# CONFIGURATION___STORAGE___USER_LEDS_BUTT.net
KiCad netlist of a schematic drawn in Altium Designer
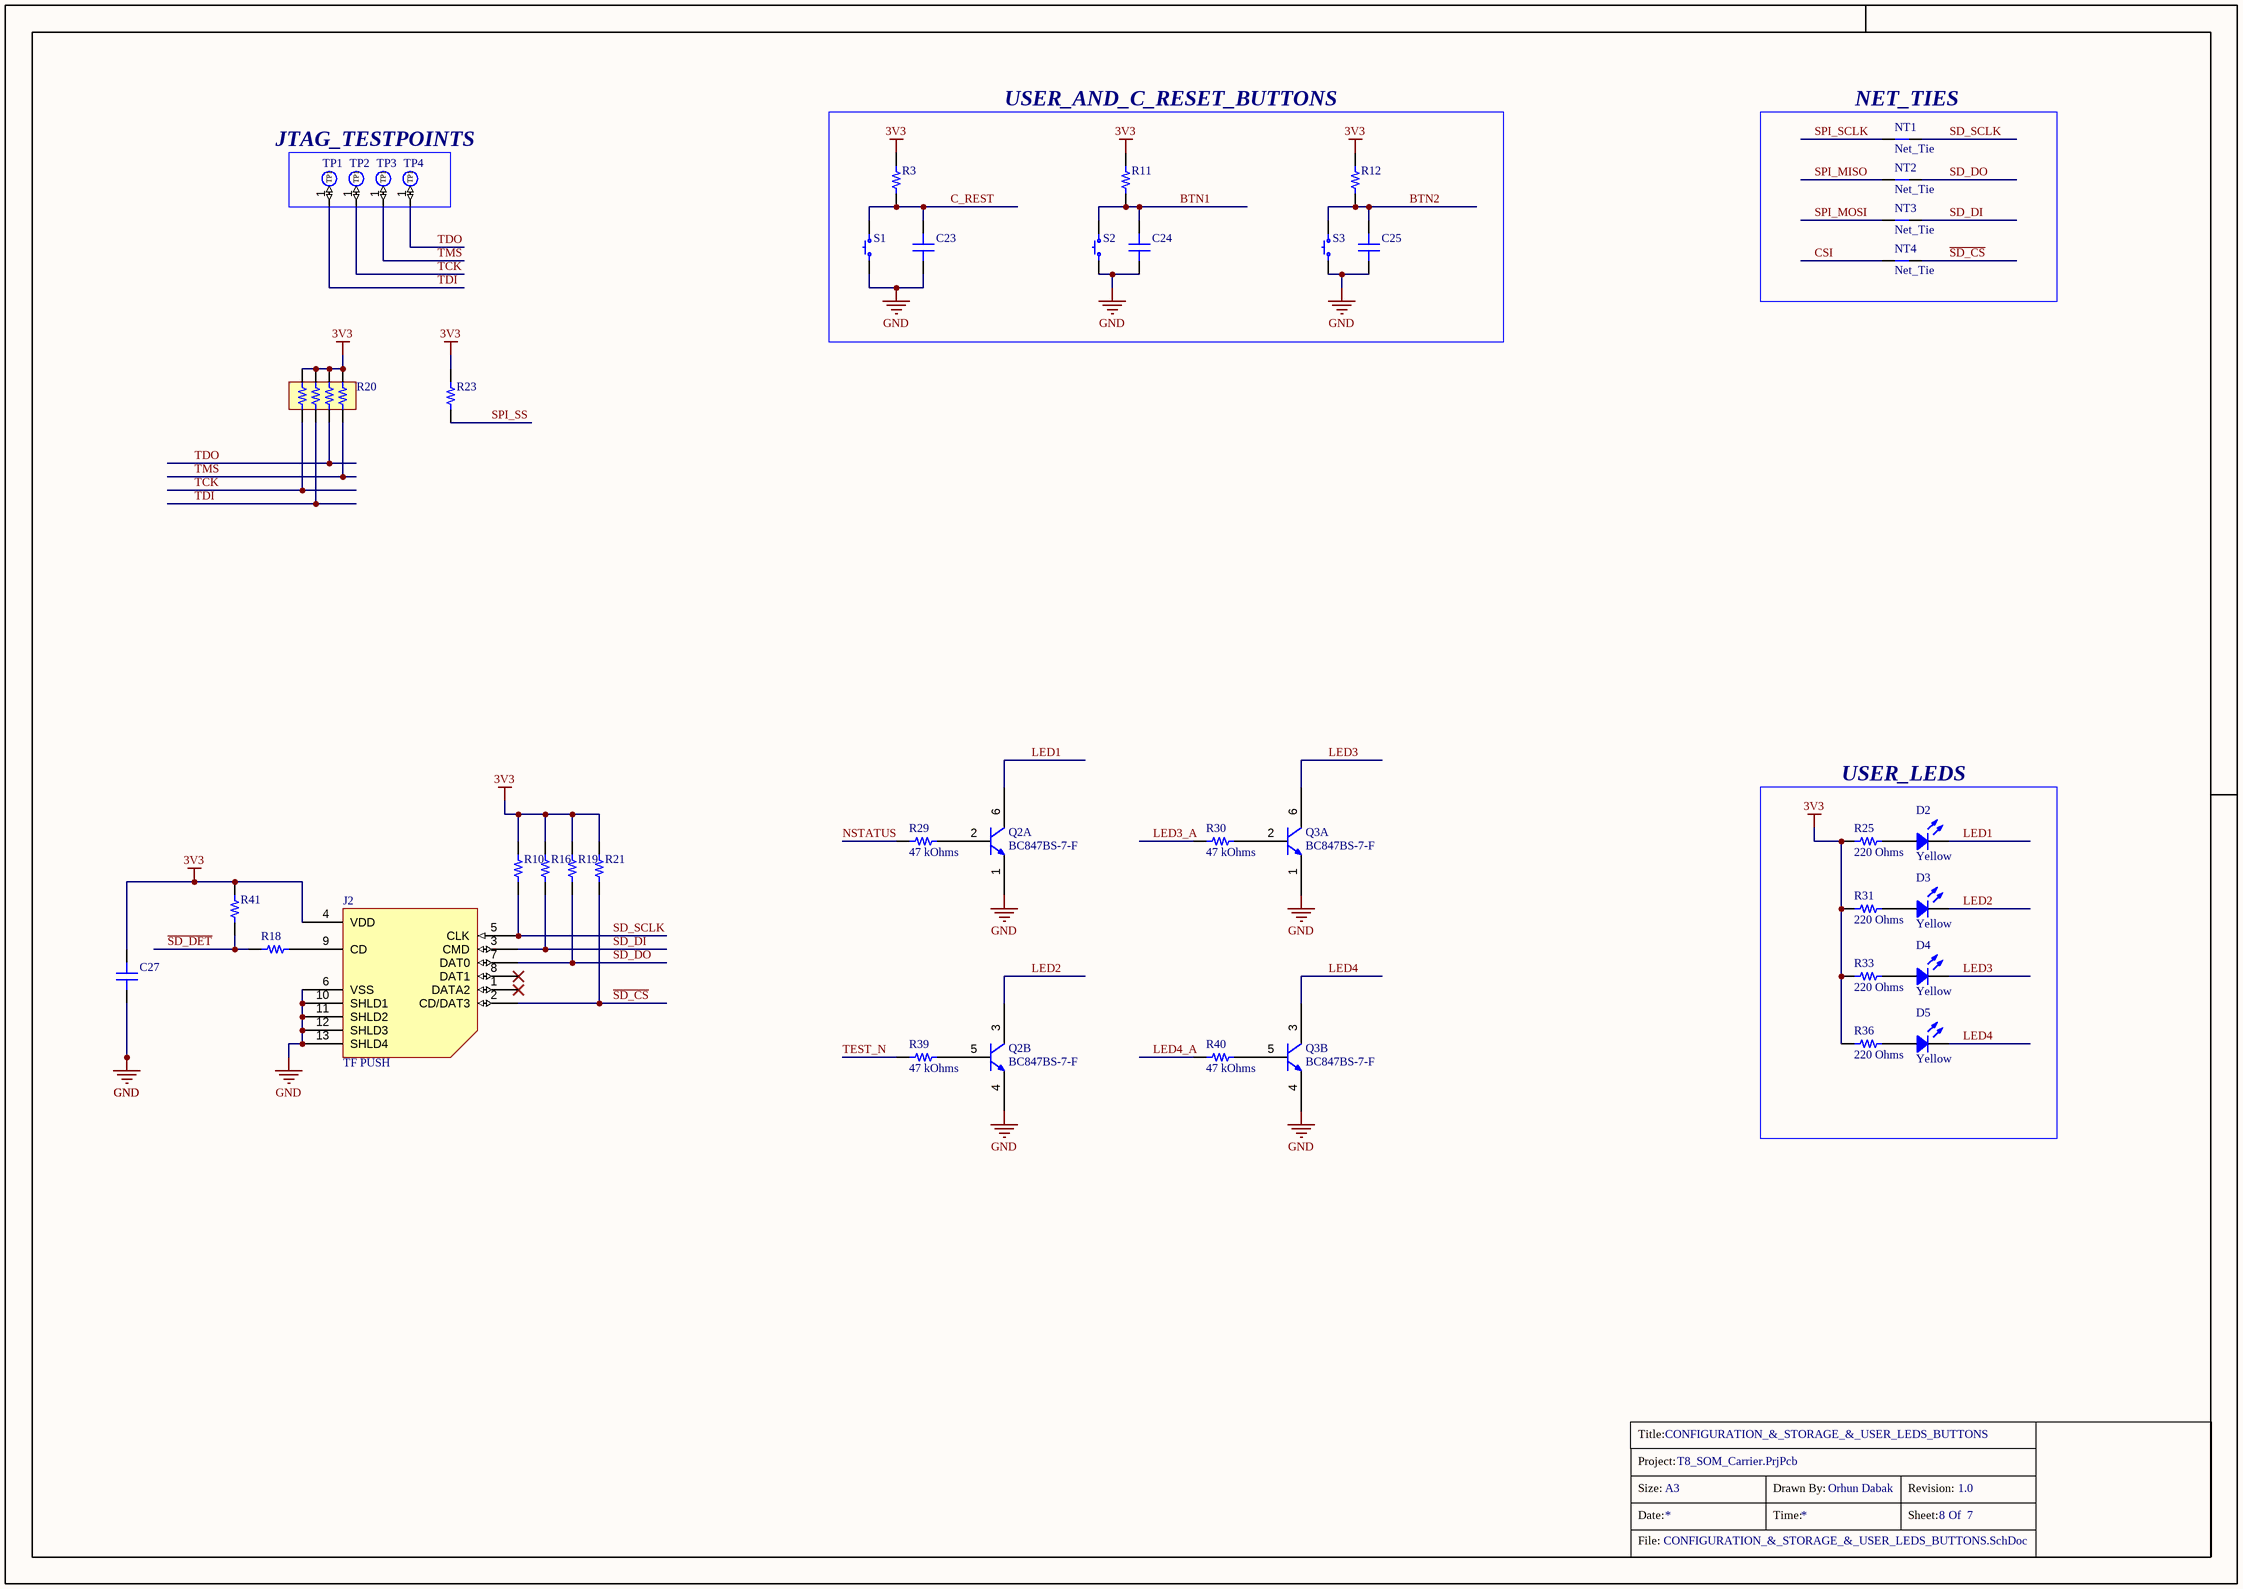
[diagram p0: CONFIGURATION_&_STORAGE_&_USER_LEDS_BUTTONS.SchDoc]

(export (version "E")
  (design (tool "Eeschema 10.0.6"))
  (components
    (comp (ref "C23")
      (value "10 µF")
      (footprint "CAP 0402_1005")
      (description "CAP CER 10UF 10V X5R 0402")
      (fields
        (field (name "PART NUMBER") "GRM155R61A106ME11D")
        (field (name "MANUFACTURER") "Murata Electronics")
      )
      (libsource (lib "Celestial Altium Library - altium_library") (part "Capacitor"))
    )
    (comp (ref "C24")
      (value "10 µF")
      (footprint "CAP 0402_1005")
      (description "CAP CER 10UF 10V X5R 0402")
      (fields
        (field (name "PART NUMBER") "GRM155R61A106ME11D")
        (field (name "MANUFACTURER") "Murata Electronics")
      )
      (libsource (lib "Celestial Altium Library - altium_library") (part "Capacitor"))
    )
    (comp (ref "C25")
      (value "10 µF")
      (footprint "CAP 0402_1005")
      (description "CAP CER 10UF 10V X5R 0402")
      (fields
        (field (name "PART NUMBER") "GRM155R61A106ME11D")
        (field (name "MANUFACTURER") "Murata Electronics")
      )
      (libsource (lib "Celestial Altium Library - altium_library") (part "Capacitor"))
    )
    (comp (ref "C27")
      (value "0.1 µF")
      (footprint "CAP 0402_1005")
      (description "CAP CER 0.1UF 10V X7R 0402")
      (fields (field (name "PART NUMBER") "CC0402KRX7R6BB104") (field (name "MANUFACTURER") "Yageo"))
      (libsource (lib "Celestial Altium Library - altium_library") (part "Capacitor"))
    )
    (comp (ref "D2")
      (value "Yellow")
      (footprint "LED 0603_1608 YELLOW")
      (description "LED YELLOW DIFFUSED SMD")
      (fields
        (field (name "PART NUMBER") "SML-LX0603YW-TR")
        (field (name "MANUFACTURER") "Lumex Opto/Components Inc.")
      )
      (libsource (lib "Celestial Altium Library - altium_library") (part "LED"))
    )
    (comp (ref "D3")
      (value "Yellow")
      (footprint "LED 0603_1608 YELLOW")
      (description "LED YELLOW DIFFUSED SMD")
      (fields
        (field (name "PART NUMBER") "SML-LX0603YW-TR")
        (field (name "MANUFACTURER") "Lumex Opto/Components Inc.")
      )
      (libsource (lib "Celestial Altium Library - altium_library") (part "LED"))
    )
    (comp (ref "D4")
      (value "Yellow")
      (footprint "LED 0603_1608 YELLOW")
      (description "LED YELLOW DIFFUSED SMD")
      (fields
        (field (name "PART NUMBER") "SML-LX0603YW-TR")
        (field (name "MANUFACTURER") "Lumex Opto/Components Inc.")
      )
      (libsource (lib "Celestial Altium Library - altium_library") (part "LED"))
    )
    (comp (ref "D5")
      (value "Yellow")
      (footprint "LED 0603_1608 YELLOW")
      (description "LED YELLOW DIFFUSED SMD")
      (fields
        (field (name "PART NUMBER") "SML-LX0603YW-TR")
        (field (name "MANUFACTURER") "Lumex Opto/Components Inc.")
      )
      (libsource (lib "Celestial Altium Library - altium_library") (part "LED"))
    )
    (comp (ref "J2")
      (value "TF PUSH")
      (footprint "TF PUSH")
      (description "-20℃~+90℃ 2mm Deck MicroSD card (TF card) Self bomb SMD SD Card Connectors ROHS")
      (fields (field (name "MANUFACTURER") "SHOU HAN") (field (name "LCSC PART NUMBER") "C393941"))
      (libsource (lib "T8_devkit_PCB") (part "TF PUSH"))
    )
    (comp (ref "NT1")
      (value "Net_Tie")
      (footprint "Net_Tie 0.2X0.2")
      (description "Net Tie")
      (libsource (lib "T8_devkit_PCB") (part "Net_Tie"))
    )
    (comp (ref "NT2")
      (value "Net_Tie")
      (footprint "Net_Tie 0.2X0.2")
      (description "Net Tie")
      (libsource (lib "T8_devkit_PCB") (part "Net_Tie"))
    )
    (comp (ref "NT3")
      (value "Net_Tie")
      (footprint "Net_Tie 0.2X0.2")
      (description "Net Tie")
      (libsource (lib "T8_devkit_PCB") (part "Net_Tie"))
    )
    (comp (ref "NT4")
      (value "Net_Tie")
      (footprint "Net_Tie 0.2X0.2")
      (description "Net Tie")
      (libsource (lib "T8_devkit_PCB") (part "Net_Tie"))
    )
    (comp (ref "Q2")
      (value "BC847BS-7-F")
      (footprint "BC847BS-7-F-Footprint-1")
      (description "2NPN Ic=100mA Vceo=45V hfe=200~450 P=200mW SOT363")
      (libsource (lib "Kocaeli University") (part "BC847BS-7-F-Symbol-1"))
    )
    (comp (ref "Q3")
      (value "BC847BS-7-F")
      (footprint "BC847BS-7-F-Footprint-1")
      (description "2NPN Ic=100mA Vceo=45V hfe=200~450 P=200mW SOT363")
      (libsource (lib "Kocaeli University") (part "BC847BS-7-F-Symbol-1"))
    )
    (comp (ref "R3")
      (value "10 kOhms")
      (footprint "RES 0201_0603")
      (description "RES 10K OHM 1% 1/20W 0201")
      (fields (field (name "PART NUMBER") "RC0201FR-0710KL") (field (name "MANUFACTURER") "Yageo"))
      (libsource (lib "Celestial Altium Library - altium_library") (part "Resistor"))
    )
    (comp (ref "R10")
      (value "10 kOhms")
      (footprint "RES 0201_0603")
      (description "RES SMD 10K OHM 1% 1/20W 0201")
      (fields (field (name "PART NUMBER") "CRCW020110K0FKED") (field (name "MANUFACTURER") "Vishay Dale"))
      (libsource (lib "Celestial Altium Library - altium_library") (part "Resistor"))
    )
    (comp (ref "R11")
      (value "10 kOhms")
      (footprint "RES 0201_0603")
      (description "RES 10K OHM 1% 1/20W 0201")
      (fields (field (name "PART NUMBER") "RC0201FR-0710KL") (field (name "MANUFACTURER") "Yageo"))
      (libsource (lib "Celestial Altium Library - altium_library") (part "Resistor"))
    )
    (comp (ref "R12")
      (value "10 kOhms")
      (footprint "RES 0201_0603")
      (description "RES 10K OHM 1% 1/20W 0201")
      (fields (field (name "PART NUMBER") "RC0201FR-0710KL") (field (name "MANUFACTURER") "Yageo"))
      (libsource (lib "Celestial Altium Library - altium_library") (part "Resistor"))
    )
    (comp (ref "R16")
      (value "10 kOhms")
      (footprint "RES 0201_0603")
      (description "RES SMD 10K OHM 1% 1/20W 0201")
      (fields (field (name "PART NUMBER") "CRCW020110K0FKED") (field (name "MANUFACTURER") "Vishay Dale"))
      (libsource (lib "Celestial Altium Library - altium_library") (part "Resistor"))
    )
    (comp (ref "R18")
      (value "0 Ohms")
      (footprint "RES 0201_0603")
      (description "RES 0 OHM JUMPER 1/20W 0201")
      (fields (field (name "PART NUMBER") "RC0201JR-070RL") (field (name "MANUFACTURER") "Yageo"))
      (libsource (lib "Celestial Altium Library - altium_library") (part "Resistor"))
    )
    (comp (ref "R19")
      (value "10 kOhms")
      (footprint "RES 0201_0603")
      (description "RES SMD 10K OHM 1% 1/20W 0201")
      (fields (field (name "PART NUMBER") "CRCW020110K0FKED") (field (name "MANUFACTURER") "Vishay Dale"))
      (libsource (lib "Celestial Altium Library - altium_library") (part "Resistor"))
    )
    (comp (ref "R20")
      (value "YC124-JR-0710KL")
      (footprint "RESNET 0804-8 CONVEX")
      (description "RES ARRAY 4 RES 10K OHM 0804")
      (fields (field (name "MANUFACTURER") "Yageo") (field (name "TOLERANCE") "±5%"))
      (libsource (lib "Celestial Altium Library - altium_library") (part "Resistor Array (4 circuit)"))
    )
    (comp (ref "R21")
      (value "10 kOhms")
      (footprint "RES 0201_0603")
      (description "RES SMD 10K OHM 1% 1/20W 0201")
      (fields (field (name "PART NUMBER") "CRCW020110K0FKED") (field (name "MANUFACTURER") "Vishay Dale"))
      (libsource (lib "Celestial Altium Library - altium_library") (part "Resistor"))
    )
    (comp (ref "R23")
      (value "10 kOhms")
      (footprint "RES 0201_0603")
      (description "RES 10K OHM 1% 1/20W 0201")
      (fields (field (name "PART NUMBER") "RC0201FR-0710KL") (field (name "MANUFACTURER") "Yageo"))
      (libsource (lib "Celestial Altium Library - altium_library") (part "Resistor"))
    )
    (comp (ref "R25")
      (value "220 Ohms")
      (footprint "RES 0402_1005")
      (description "RES 220 OHM 1% 1/16W 0402")
      (fields (field (name "PART NUMBER") "RC0402FR-07220RL") (field (name "MANUFACTURER") "Yageo"))
      (libsource (lib "Celestial Altium Library - altium_library") (part "Resistor"))
    )
    (comp (ref "R29")
      (value "47 kOhms")
      (footprint "RES 0201_0603")
      (description "RES 47K OHM 1% 1/20W 0201")
      (fields (field (name "PART NUMBER") "RC0201FR-0747KL") (field (name "MANUFACTURER") "Yageo"))
      (libsource (lib "Celestial Altium Library - altium_library") (part "Resistor"))
    )
    (comp (ref "R30")
      (value "47 kOhms")
      (footprint "RES 0201_0603")
      (description "RES 47K OHM 1% 1/20W 0201")
      (fields (field (name "PART NUMBER") "RC0201FR-0747KL") (field (name "MANUFACTURER") "Yageo"))
      (libsource (lib "Celestial Altium Library - altium_library") (part "Resistor"))
    )
    (comp (ref "R31")
      (value "220 Ohms")
      (footprint "RES 0402_1005")
      (description "RES 220 OHM 1% 1/16W 0402")
      (fields (field (name "PART NUMBER") "RC0402FR-07220RL") (field (name "MANUFACTURER") "Yageo"))
      (libsource (lib "Celestial Altium Library - altium_library") (part "Resistor"))
    )
    (comp (ref "R33")
      (value "220 Ohms")
      (footprint "RES 0402_1005")
      (description "RES 220 OHM 1% 1/16W 0402")
      (fields (field (name "PART NUMBER") "RC0402FR-07220RL") (field (name "MANUFACTURER") "Yageo"))
      (libsource (lib "Celestial Altium Library - altium_library") (part "Resistor"))
    )
    (comp (ref "R36")
      (value "220 Ohms")
      (footprint "RES 0402_1005")
      (description "RES 220 OHM 1% 1/16W 0402")
      (fields (field (name "PART NUMBER") "RC0402FR-07220RL") (field (name "MANUFACTURER") "Yageo"))
      (libsource (lib "Celestial Altium Library - altium_library") (part "Resistor"))
    )
    (comp (ref "R39")
      (value "47 kOhms")
      (footprint "RES 0201_0603")
      (description "RES 47K OHM 1% 1/20W 0201")
      (fields (field (name "PART NUMBER") "RC0201FR-0747KL") (field (name "MANUFACTURER") "Yageo"))
      (libsource (lib "Celestial Altium Library - altium_library") (part "Resistor"))
    )
    (comp (ref "R40")
      (value "47 kOhms")
      (footprint "RES 0201_0603")
      (description "RES 47K OHM 1% 1/20W 0201")
      (fields (field (name "PART NUMBER") "RC0201FR-0747KL") (field (name "MANUFACTURER") "Yageo"))
      (libsource (lib "Celestial Altium Library - altium_library") (part "Resistor"))
    )
    (comp (ref "R41")
      (value "100 kOhms")
      (footprint "RES 0201_0603")
      (description "RES SMD 100K OHM 1% 1/20W 0201")
      (fields
        (field (name "PART NUMBER") "CRG0201F100K")
        (field (name "MANUFACTURER") "TE Connectivity Passive Product")
      )
      (libsource (lib "Celestial Altium Library - altium_library") (part "Resistor"))
    )
    (comp (ref "S1")
      (value "TS342A2P-WZ")
      (footprint "TS342A2P-WZ")
      (fields (field (name "MANUFACTURER") "SHOU HAN") (field (name "JLCPCB PART NUMBER") "C557591"))
      (libsource (lib "T8_devkit_PCB") (part "TS342A2P-WZ"))
    )
    (comp (ref "S2")
      (value "TS342A2P-WZ")
      (footprint "TS342A2P-WZ")
      (fields (field (name "MANUFACTURER") "SHOU HAN") (field (name "JLCPCB PART NUMBER") "C557591"))
      (libsource (lib "T8_devkit_PCB") (part "TS342A2P-WZ"))
    )
    (comp (ref "S3")
      (value "TS342A2P-WZ")
      (footprint "TS342A2P-WZ")
      (fields (field (name "MANUFACTURER") "SHOU HAN") (field (name "JLCPCB PART NUMBER") "C557591"))
      (libsource (lib "T8_devkit_PCB") (part "TS342A2P-WZ"))
    )
    (comp (ref "TP1")
      (value "TP_1")
      (footprint "TEST POINT")
      (description "1.5x1.5mm Test Point(I/O)")
      (libsource (lib "FPGA_Based_SOM") (part "TEST POINT_1(I/O)"))
    )
    (comp (ref "TP2")
      (value "TP_1")
      (footprint "TEST POINT")
      (description "1.5x1.5mm Test Point(I/O)")
      (libsource (lib "FPGA_Based_SOM") (part "TEST POINT_1(I/O)"))
    )
    (comp (ref "TP3")
      (value "TP_1")
      (footprint "TEST POINT")
      (description "1.5x1.5mm Test Point(I/O)")
      (libsource (lib "FPGA_Based_SOM") (part "TEST POINT_1(I/O)"))
    )
    (comp (ref "TP4")
      (value "TP_1")
      (footprint "TEST POINT")
      (description "1.5x1.5mm Test Point(I/O)")
      (libsource (lib "FPGA_Based_SOM") (part "TEST POINT_1(I/O)"))
    )
  )
  (nets
    (net (code "1") (name "/BTN1") (class "Default")
      (node (ref "C24") (pin "2") (pinfunction "2_2") (pintype "passive"))
      (node (ref "R11") (pin "1") (pinfunction "1_1") (pintype "passive"))
      (node (ref "S2") (pin "2") (pinfunction "2_2") (pintype "passive"))
    )
    (net (code "2") (name "/BTN2") (class "Default")
      (node (ref "C25") (pin "2") (pinfunction "2_2") (pintype "passive"))
      (node (ref "R12") (pin "1") (pinfunction "1_1") (pintype "passive"))
      (node (ref "S3") (pin "2") (pinfunction "2_2") (pintype "passive"))
    )
    (net (code "3") (name "/CSI") (class "Default") (node (ref "NT4") (pin "1") (pintype "passive")))
    (net (code "4") (name "/C_REST") (class "Default")
      (node (ref "C23") (pin "2") (pinfunction "2_2") (pintype "passive"))
      (node (ref "R3") (pin "1") (pinfunction "1_1") (pintype "passive"))
      (node (ref "S1") (pin "2") (pinfunction "2_2") (pintype "passive"))
    )
    (net (code "5") (name "/LED1") (class "Default")
      (node (ref "D2") (pin "2") (pinfunction "2_2") (pintype "passive"))
      (node (ref "Q2") (pin "6") (pinfunction "Collector_6") (pintype "passive"))
    )
    (net (code "6") (name "/LED2") (class "Default")
      (node (ref "D3") (pin "2") (pinfunction "2_2") (pintype "passive"))
      (node (ref "Q2") (pin "3") (pinfunction "Collector_3") (pintype "passive"))
    )
    (net (code "7") (name "/LED3") (class "Default")
      (node (ref "D4") (pin "2") (pinfunction "2_2") (pintype "passive"))
      (node (ref "Q3") (pin "6") (pinfunction "Collector_6") (pintype "passive"))
    )
    (net (code "8") (name "/LED3_A") (class "Default")
      (node (ref "R30") (pin "1") (pinfunction "1_1") (pintype "passive"))
    )
    (net (code "9") (name "/LED4") (class "Default")
      (node (ref "D5") (pin "2") (pinfunction "2_2") (pintype "passive"))
      (node (ref "Q3") (pin "3") (pinfunction "Collector_3") (pintype "passive"))
    )
    (net (code "10") (name "/LED4_A") (class "Default")
      (node (ref "R40") (pin "1") (pinfunction "1_1") (pintype "passive"))
    )
    (net (code "11") (name "/NSTATUS") (class "Default")
      (node (ref "R29") (pin "1") (pinfunction "1_1") (pintype "passive"))
    )
    (net (code "12") (name "/SD_DI") (class "Default")
      (node (ref "J2") (pin "3") (pinfunction "CMD_3") (pintype "bidirectional"))
      (node (ref "NT3") (pin "2") (pintype "passive"))
      (node (ref "R16") (pin "1") (pinfunction "1_1") (pintype "passive"))
    )
    (net (code "13") (name "/SD_DO") (class "Default")
      (node (ref "J2") (pin "7") (pinfunction "DAT0_7") (pintype "bidirectional"))
      (node (ref "NT2") (pin "2") (pintype "passive"))
      (node (ref "R19") (pin "1") (pinfunction "1_1") (pintype "passive"))
    )
    (net (code "14") (name "/SD_SCLK") (class "Default")
      (node (ref "J2") (pin "5") (pinfunction "CLK_5") (pintype "input"))
      (node (ref "NT1") (pin "2") (pintype "passive"))
      (node (ref "R10") (pin "1") (pinfunction "1_1") (pintype "passive"))
    )
    (net (code "15") (name "/SPI_MISO") (class "Default") (node (ref "NT2") (pin "1") (pintype "passive")))
    (net (code "16") (name "/SPI_MOSI") (class "Default") (node (ref "NT3") (pin "1") (pintype "passive")))
    (net (code "17") (name "/SPI_SCLK") (class "Default") (node (ref "NT1") (pin "1") (pintype "passive")))
    (net (code "18") (name "/SPI_SS") (class "Default")
      (node (ref "R23") (pin "1") (pinfunction "1_1") (pintype "passive"))
    )
    (net (code "19") (name "/TCK") (class "Default")
      (node (ref "R20") (pin "1") (pinfunction "1_1") (pintype "passive"))
      (node (ref "TP2") (pin "1") (pinfunction "TP1_1") (pintype "bidirectional"))
    )
    (net (code "20") (name "/TDI") (class "Default")
      (node (ref "R20") (pin "2") (pinfunction "2_2") (pintype "passive"))
      (node (ref "TP1") (pin "1") (pinfunction "TP1_1") (pintype "bidirectional"))
    )
    (net (code "21") (name "/TDO") (class "Default")
      (node (ref "R20") (pin "3") (pinfunction "3_3") (pintype "passive"))
      (node (ref "TP4") (pin "1") (pinfunction "TP1_1") (pintype "bidirectional"))
    )
    (net (code "22") (name "/TEST_N") (class "Default")
      (node (ref "R39") (pin "1") (pinfunction "1_1") (pintype "passive"))
    )
    (net (code "23") (name "/TMS") (class "Default")
      (node (ref "R20") (pin "4") (pinfunction "4_4") (pintype "passive"))
      (node (ref "TP3") (pin "1") (pinfunction "TP1_1") (pintype "bidirectional"))
    )
    (net (code "24") (name "/~{SD_CS}") (class "Default")
      (node (ref "J2") (pin "2") (pinfunction "CD/DAT3_2") (pintype "bidirectional"))
      (node (ref "NT4") (pin "2") (pintype "passive"))
      (node (ref "R21") (pin "1") (pinfunction "1_1") (pintype "passive"))
    )
    (net (code "25") (name "/~{SD_DET}") (class "Default")
      (node (ref "R18") (pin "1") (pinfunction "1_1") (pintype "passive"))
      (node (ref "R41") (pin "1") (pinfunction "1_1") (pintype "passive"))
    )
    (net (code "26") (name "3V3") (class "Default")
      (node (ref "C27") (pin "2") (pinfunction "2_2") (pintype "passive"))
      (node (ref "J2") (pin "4") (pinfunction "VDD_4") (pintype "power_in"))
      (node (ref "R10") (pin "2") (pinfunction "2_2") (pintype "passive"))
      (node (ref "R11") (pin "2") (pinfunction "2_2") (pintype "passive"))
      (node (ref "R12") (pin "2") (pinfunction "2_2") (pintype "passive"))
      (node (ref "R16") (pin "2") (pinfunction "2_2") (pintype "passive"))
      (node (ref "R19") (pin "2") (pinfunction "2_2") (pintype "passive"))
      (node (ref "R20") (pin "5") (pinfunction "5_5") (pintype "passive"))
      (node (ref "R20") (pin "6") (pinfunction "6_6") (pintype "passive"))
      (node (ref "R20") (pin "7") (pinfunction "7_7") (pintype "passive"))
      (node (ref "R20") (pin "8") (pinfunction "8_8") (pintype "passive"))
      (node (ref "R21") (pin "2") (pinfunction "2_2") (pintype "passive"))
      (node (ref "R23") (pin "2") (pinfunction "2_2") (pintype "passive"))
      (node (ref "R25") (pin "1") (pinfunction "1_1") (pintype "passive"))
      (node (ref "R3") (pin "2") (pinfunction "2_2") (pintype "passive"))
      (node (ref "R31") (pin "1") (pinfunction "1_1") (pintype "passive"))
      (node (ref "R33") (pin "1") (pinfunction "1_1") (pintype "passive"))
      (node (ref "R36") (pin "1") (pinfunction "1_1") (pintype "passive"))
      (node (ref "R41") (pin "2") (pinfunction "2_2") (pintype "passive"))
    )
    (net (code "27") (name "GND") (class "Default")
      (node (ref "C23") (pin "1") (pinfunction "1_1") (pintype "passive"))
      (node (ref "C24") (pin "1") (pinfunction "1_1") (pintype "passive"))
      (node (ref "C25") (pin "1") (pinfunction "1_1") (pintype "passive"))
      (node (ref "C27") (pin "1") (pinfunction "1_1") (pintype "passive"))
      (node (ref "J2") (pin "10") (pinfunction "SHLD1_10") (pintype "passive"))
      (node (ref "J2") (pin "11") (pinfunction "SHLD2_11") (pintype "passive"))
      (node (ref "J2") (pin "12") (pinfunction "SHLD3_12") (pintype "passive"))
      (node (ref "J2") (pin "13") (pinfunction "SHLD4_13") (pintype "passive"))
      (node (ref "J2") (pin "6") (pinfunction "VSS_6") (pintype "power_in"))
      (node (ref "Q2") (pin "1") (pinfunction "Emitter_1") (pintype "passive"))
      (node (ref "Q2") (pin "4") (pinfunction "Emitter_4") (pintype "passive"))
      (node (ref "Q3") (pin "1") (pinfunction "Emitter_1") (pintype "passive"))
      (node (ref "Q3") (pin "4") (pinfunction "Emitter_4") (pintype "passive"))
      (node (ref "S1") (pin "1") (pinfunction "1_1") (pintype "passive"))
      (node (ref "S2") (pin "1") (pinfunction "1_1") (pintype "passive"))
      (node (ref "S3") (pin "1") (pinfunction "1_1") (pintype "passive"))
    )
    (net (code "28") (name "Net-(D2-Pad1)") (class "Default")
      (node (ref "D2") (pin "1") (pinfunction "1_1") (pintype "passive"))
      (node (ref "R25") (pin "2") (pinfunction "2_2") (pintype "passive"))
    )
    (net (code "29") (name "Net-(D3-Pad1)") (class "Default")
      (node (ref "D3") (pin "1") (pinfunction "1_1") (pintype "passive"))
      (node (ref "R31") (pin "2") (pinfunction "2_2") (pintype "passive"))
    )
    (net (code "30") (name "Net-(D4-Pad1)") (class "Default")
      (node (ref "D4") (pin "1") (pinfunction "1_1") (pintype "passive"))
      (node (ref "R33") (pin "2") (pinfunction "2_2") (pintype "passive"))
    )
    (net (code "31") (name "Net-(D5-Pad1)") (class "Default")
      (node (ref "D5") (pin "1") (pinfunction "1_1") (pintype "passive"))
      (node (ref "R36") (pin "2") (pinfunction "2_2") (pintype "passive"))
    )
    (net (code "32") (name "Net-(J2-CD)") (class "Default")
      (node (ref "J2") (pin "9") (pinfunction "CD_9") (pintype "passive"))
      (node (ref "R18") (pin "2") (pinfunction "2_2") (pintype "passive"))
    )
    (net (code "33") (name "Net-(Q2A-Base)") (class "Default")
      (node (ref "Q2") (pin "2") (pinfunction "Base_2") (pintype "passive"))
      (node (ref "R29") (pin "2") (pinfunction "2_2") (pintype "passive"))
    )
    (net (code "34") (name "Net-(Q2B-Base)") (class "Default")
      (node (ref "Q2") (pin "5") (pinfunction "Base_5") (pintype "passive"))
      (node (ref "R39") (pin "2") (pinfunction "2_2") (pintype "passive"))
    )
    (net (code "35") (name "Net-(Q3A-Base)") (class "Default")
      (node (ref "Q3") (pin "2") (pinfunction "Base_2") (pintype "passive"))
      (node (ref "R30") (pin "2") (pinfunction "2_2") (pintype "passive"))
    )
    (net (code "36") (name "Net-(Q3B-Base)") (class "Default")
      (node (ref "Q3") (pin "5") (pinfunction "Base_5") (pintype "passive"))
      (node (ref "R40") (pin "2") (pinfunction "2_2") (pintype "passive"))
    )
    (net (code "37") (name "unconnected-(J2-DAT1-Pad8)") (class "Default")
      (node (ref "J2") (pin "8") (pinfunction "DAT1_8") (pintype "bidirectional+no_connect"))
    )
    (net (code "38") (name "unconnected-(J2-DATA2-Pad1)") (class "Default")
      (node (ref "J2") (pin "1") (pinfunction "DATA2_1") (pintype "bidirectional+no_connect"))
    )
  )
)
